# NodeMCU.net
KiCad netlist of a schematic drawn in EAGLE
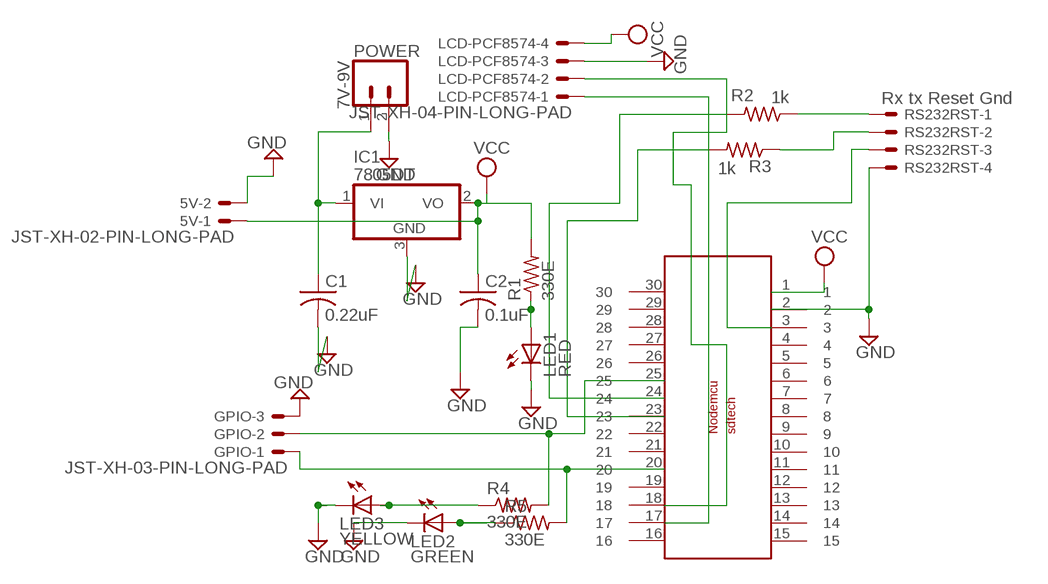
[diagram p0: schematic, sheet 1]

(export (version "E")
  (design (tool "Eeschema 10.0.6"))
  (components
    (comp (ref "5V")
      (value "JST-XH-02-PIN-LONG-PAD")
      (footprint "eagle-import:JST-XH-02-PACKAGE-LONG-PAD")
      (libsource (lib "eagle-import") (part "JST-XH-02-PIN-LONG-PAD"))
    )
    (comp (ref "C1")
      (value "0.22uF")
      (footprint "eagle-import:C0805K")
      (libsource (lib "eagle-import") (part "C-USC0805K"))
    )
    (comp (ref "C2")
      (value "0.1uF")
      (footprint "eagle-import:C0805K")
      (libsource (lib "eagle-import") (part "C-USC0805K"))
    )
    (comp (ref "GPIO")
      (value "JST-XH-03-PIN-LONG-PAD")
      (footprint "eagle-import:JST-XH-03-PACKAGE-LONG-PAD")
      (libsource (lib "eagle-import") (part "JST-XH-03-PIN-LONG-PAD"))
    )
    (comp (ref "IC1")
      (value "7805DT")
      (footprint "eagle-import:TO252")
      (libsource (lib "eagle-import") (part "78DT05"))
    )
    (comp (ref "LCD-PCF8574")
      (value "JST-XH-04-PIN-LONG-PAD")
      (footprint "eagle-import:JST-XH-04-PACKAGE-LONG-PAD")
      (libsource (lib "eagle-import") (part "JST-XH-04-PIN-LONG-PAD"))
    )
    (comp (ref "LED1")
      (value "RED")
      (footprint "eagle-import:CHIPLED_0805")
      (libsource (lib "eagle-import") (part "LEDCHIPLED_0805"))
    )
    (comp (ref "LED2")
      (value "GREEN")
      (footprint "eagle-import:CHIPLED_0805")
      (libsource (lib "eagle-import") (part "LEDCHIPLED_0805"))
    )
    (comp (ref "LED3")
      (value "YELLOW")
      (footprint "eagle-import:CHIPLED_0805")
      (libsource (lib "eagle-import") (part "LEDCHIPLED_0805"))
    )
    (comp (ref "POWER")
      (value "7V-9V")
      (footprint "eagle-import:SCREWTERMINAL-5MM-2")
      (libsource (lib "eagle-import") (part "CONN_025MM"))
    )
    (comp (ref "R1")
      (value "330E")
      (footprint "eagle-import:M0805")
      (libsource (lib "eagle-import") (part "R-US_M0805"))
    )
    (comp (ref "R2")
      (value "1k")
      (footprint "eagle-import:M0805")
      (libsource (lib "eagle-import") (part "R-US_M0805"))
    )
    (comp (ref "R3")
      (value "1k")
      (footprint "eagle-import:M0805")
      (libsource (lib "eagle-import") (part "R-US_M0805"))
    )
    (comp (ref "R4")
      (value "330E")
      (footprint "eagle-import:M0805")
      (libsource (lib "eagle-import") (part "R-US_M0805"))
    )
    (comp (ref "R5")
      (value "330E")
      (footprint "eagle-import:M0805")
      (libsource (lib "eagle-import") (part "R-US_M0805"))
    )
    (comp (ref "RS232RST")
      (value "Rx tx Reset Gnd")
      (footprint "eagle-import:JST-XH-04-PACKAGE-LONG-PAD")
      (libsource (lib "eagle-import") (part "JST-XH-04-PIN-LONG-PAD"))
    )
    (comp (ref "U$2")
      (value "NodeMCU-ESP12E")
      (footprint "eagle-import:NODEMCUESP8266")
      (libsource (lib "eagle-import") (part "NODEMCUESP8266"))
    )
  )
  (nets
    (net (code "1") (name "GND") (class "Default")
      (node (ref "5V") (pin "2") (pinfunction "S_2") (pintype "passive"))
      (node (ref "C1") (pin "2") (pinfunction "2_2") (pintype "passive"))
      (node (ref "C2") (pin "2") (pinfunction "2_2") (pintype "passive"))
      (node (ref "GPIO") (pin "3") (pinfunction "S_3") (pintype "passive"))
      (node (ref "IC1") (pin "3") (pinfunction "GND_3") (pintype "passive"))
      (node (ref "LCD-PCF8574") (pin "3") (pinfunction "S_3") (pintype "passive"))
      (node (ref "LED1") (pin "C") (pinfunction "C_C") (pintype "passive"))
      (node (ref "LED2") (pin "C") (pinfunction "C_C") (pintype "passive"))
      (node (ref "LED3") (pin "C") (pinfunction "C_C") (pintype "passive"))
      (node (ref "POWER") (pin "2") (pinfunction "2_2") (pintype "passive"))
      (node (ref "RS232RST") (pin "4") (pinfunction "S_4") (pintype "passive"))
      (node (ref "U$2") (pin "2") (pinfunction "2_2") (pintype "bidirectional"))
    )
    (net (code "2") (name "Net-(GPIOA-S)") (class "Default")
      (node (ref "GPIO") (pin "1") (pinfunction "S_1") (pintype "passive"))
      (node (ref "R5") (pin "2") (pinfunction "2_2") (pintype "passive"))
      (node (ref "U$2") (pin "20") (pinfunction "20_20") (pintype "bidirectional"))
    )
    (net (code "3") (name "Net-(GPIOB-S)") (class "Default")
      (node (ref "GPIO") (pin "2") (pinfunction "S_2") (pintype "passive"))
      (node (ref "R4") (pin "2") (pinfunction "2_2") (pintype "passive"))
      (node (ref "U$2") (pin "25") (pinfunction "25_25") (pintype "bidirectional"))
    )
    (net (code "4") (name "Net-(IC1-VI)") (class "Default")
      (node (ref "C1") (pin "1") (pinfunction "1_1") (pintype "passive"))
      (node (ref "IC1") (pin "1") (pinfunction "VI_1") (pintype "input"))
      (node (ref "POWER") (pin "1") (pinfunction "1_1") (pintype "passive"))
    )
    (net (code "5") (name "Net-(LCD-PCF8574A-S)") (class "Default")
      (node (ref "LCD-PCF8574") (pin "1") (pinfunction "S_1") (pintype "passive"))
      (node (ref "U$2") (pin "17") (pinfunction "17_17") (pintype "bidirectional"))
    )
    (net (code "6") (name "Net-(LCD-PCF8574B-S)") (class "Default")
      (node (ref "LCD-PCF8574") (pin "2") (pinfunction "S_2") (pintype "passive"))
      (node (ref "U$2") (pin "18") (pinfunction "18_18") (pintype "bidirectional"))
    )
    (net (code "7") (name "Net-(LED1-PadA)") (class "Default")
      (node (ref "LED1") (pin "A") (pinfunction "A_A") (pintype "passive"))
      (node (ref "R1") (pin "1") (pinfunction "1_1") (pintype "passive"))
    )
    (net (code "8") (name "Net-(LED2-PadA)") (class "Default")
      (node (ref "LED2") (pin "A") (pinfunction "A_A") (pintype "passive"))
      (node (ref "R5") (pin "1") (pinfunction "1_1") (pintype "passive"))
    )
    (net (code "9") (name "Net-(LED3-PadA)") (class "Default")
      (node (ref "LED3") (pin "A") (pinfunction "A_A") (pintype "passive"))
      (node (ref "R4") (pin "1") (pinfunction "1_1") (pintype "passive"))
    )
    (net (code "10") (name "Net-(R2-Pad2)") (class "Default")
      (node (ref "R2") (pin "2") (pinfunction "2_2") (pintype "passive"))
      (node (ref "U$2") (pin "24") (pinfunction "24_24") (pintype "bidirectional"))
    )
    (net (code "11") (name "Net-(R3-Pad2)") (class "Default")
      (node (ref "R3") (pin "2") (pinfunction "2_2") (pintype "passive"))
      (node (ref "U$2") (pin "23") (pinfunction "23_23") (pintype "bidirectional"))
    )
    (net (code "12") (name "Net-(RS232RSTA-S)") (class "Default")
      (node (ref "R2") (pin "1") (pinfunction "1_1") (pintype "passive"))
      (node (ref "RS232RST") (pin "1") (pinfunction "S_1") (pintype "passive"))
    )
    (net (code "13") (name "Net-(RS232RSTB-S)") (class "Default")
      (node (ref "R3") (pin "1") (pinfunction "1_1") (pintype "passive"))
      (node (ref "RS232RST") (pin "2") (pinfunction "S_2") (pintype "passive"))
    )
    (net (code "14") (name "Net-(RS232RSTC-S)") (class "Default")
      (node (ref "RS232RST") (pin "3") (pinfunction "S_3") (pintype "passive"))
      (node (ref "U$2") (pin "3") (pinfunction "3_3") (pintype "bidirectional"))
    )
    (net (code "15") (name "VCC") (class "Default")
      (node (ref "5V") (pin "1") (pinfunction "S_1") (pintype "passive"))
      (node (ref "C2") (pin "1") (pinfunction "1_1") (pintype "passive"))
      (node (ref "IC1") (pin "2") (pinfunction "VO_2") (pintype "passive"))
      (node (ref "LCD-PCF8574") (pin "4") (pinfunction "S_4") (pintype "passive"))
      (node (ref "R1") (pin "2") (pinfunction "2_2") (pintype "passive"))
      (node (ref "U$2") (pin "1") (pinfunction "1_1") (pintype "bidirectional"))
    )
    (net (code "16") (name "unconnected-(U$2-Pad4)") (class "Default")
      (node (ref "U$2") (pin "4") (pinfunction "4_4") (pintype "bidirectional"))
    )
    (net (code "17") (name "unconnected-(U$2-Pad5)") (class "Default")
      (node (ref "U$2") (pin "5") (pinfunction "5_5") (pintype "bidirectional"))
    )
    (net (code "18") (name "unconnected-(U$2-Pad6)") (class "Default")
      (node (ref "U$2") (pin "6") (pinfunction "6_6") (pintype "bidirectional"))
    )
    (net (code "19") (name "unconnected-(U$2-Pad7)") (class "Default")
      (node (ref "U$2") (pin "7") (pinfunction "7_7") (pintype "bidirectional"))
    )
    (net (code "20") (name "unconnected-(U$2-Pad8)") (class "Default")
      (node (ref "U$2") (pin "8") (pinfunction "8_8") (pintype "bidirectional"))
    )
    (net (code "21") (name "unconnected-(U$2-Pad9)") (class "Default")
      (node (ref "U$2") (pin "9") (pinfunction "9_9") (pintype "bidirectional"))
    )
    (net (code "22") (name "unconnected-(U$2-Pad10)") (class "Default")
      (node (ref "U$2") (pin "10") (pinfunction "10_10") (pintype "bidirectional"))
    )
    (net (code "23") (name "unconnected-(U$2-Pad11)") (class "Default")
      (node (ref "U$2") (pin "11") (pinfunction "11_11") (pintype "bidirectional"))
    )
    (net (code "24") (name "unconnected-(U$2-Pad12)") (class "Default")
      (node (ref "U$2") (pin "12") (pinfunction "12_12") (pintype "bidirectional"))
    )
    (net (code "25") (name "unconnected-(U$2-Pad13)") (class "Default")
      (node (ref "U$2") (pin "13") (pinfunction "13_13") (pintype "bidirectional"))
    )
    (net (code "26") (name "unconnected-(U$2-Pad14)") (class "Default")
      (node (ref "U$2") (pin "14") (pinfunction "14_14") (pintype "bidirectional"))
    )
    (net (code "27") (name "unconnected-(U$2-Pad15)") (class "Default")
      (node (ref "U$2") (pin "15") (pinfunction "15_15") (pintype "bidirectional"))
    )
    (net (code "28") (name "unconnected-(U$2-Pad16)") (class "Default")
      (node (ref "U$2") (pin "16") (pinfunction "16_16") (pintype "bidirectional"))
    )
    (net (code "29") (name "unconnected-(U$2-Pad19)") (class "Default")
      (node (ref "U$2") (pin "19") (pinfunction "19_19") (pintype "bidirectional"))
    )
    (net (code "30") (name "unconnected-(U$2-Pad21)") (class "Default")
      (node (ref "U$2") (pin "21") (pinfunction "21_21") (pintype "bidirectional"))
    )
    (net (code "31") (name "unconnected-(U$2-Pad22)") (class "Default")
      (node (ref "U$2") (pin "22") (pinfunction "22_22") (pintype "bidirectional"))
    )
    (net (code "32") (name "unconnected-(U$2-Pad26)") (class "Default")
      (node (ref "U$2") (pin "26") (pinfunction "26_26") (pintype "bidirectional"))
    )
    (net (code "33") (name "unconnected-(U$2-Pad27)") (class "Default")
      (node (ref "U$2") (pin "27") (pinfunction "27_27") (pintype "bidirectional"))
    )
    (net (code "34") (name "unconnected-(U$2-Pad28)") (class "Default")
      (node (ref "U$2") (pin "28") (pinfunction "28_28") (pintype "bidirectional"))
    )
    (net (code "35") (name "unconnected-(U$2-Pad29)") (class "Default")
      (node (ref "U$2") (pin "29") (pinfunction "29_29") (pintype "bidirectional"))
    )
    (net (code "36") (name "unconnected-(U$2-Pad30)") (class "Default")
      (node (ref "U$2") (pin "30") (pinfunction "30_30") (pintype "bidirectional"))
    )
  )
)
